# simple_sstc_halfbridge.net
KiCad netlist of a schematic drawn in EAGLE
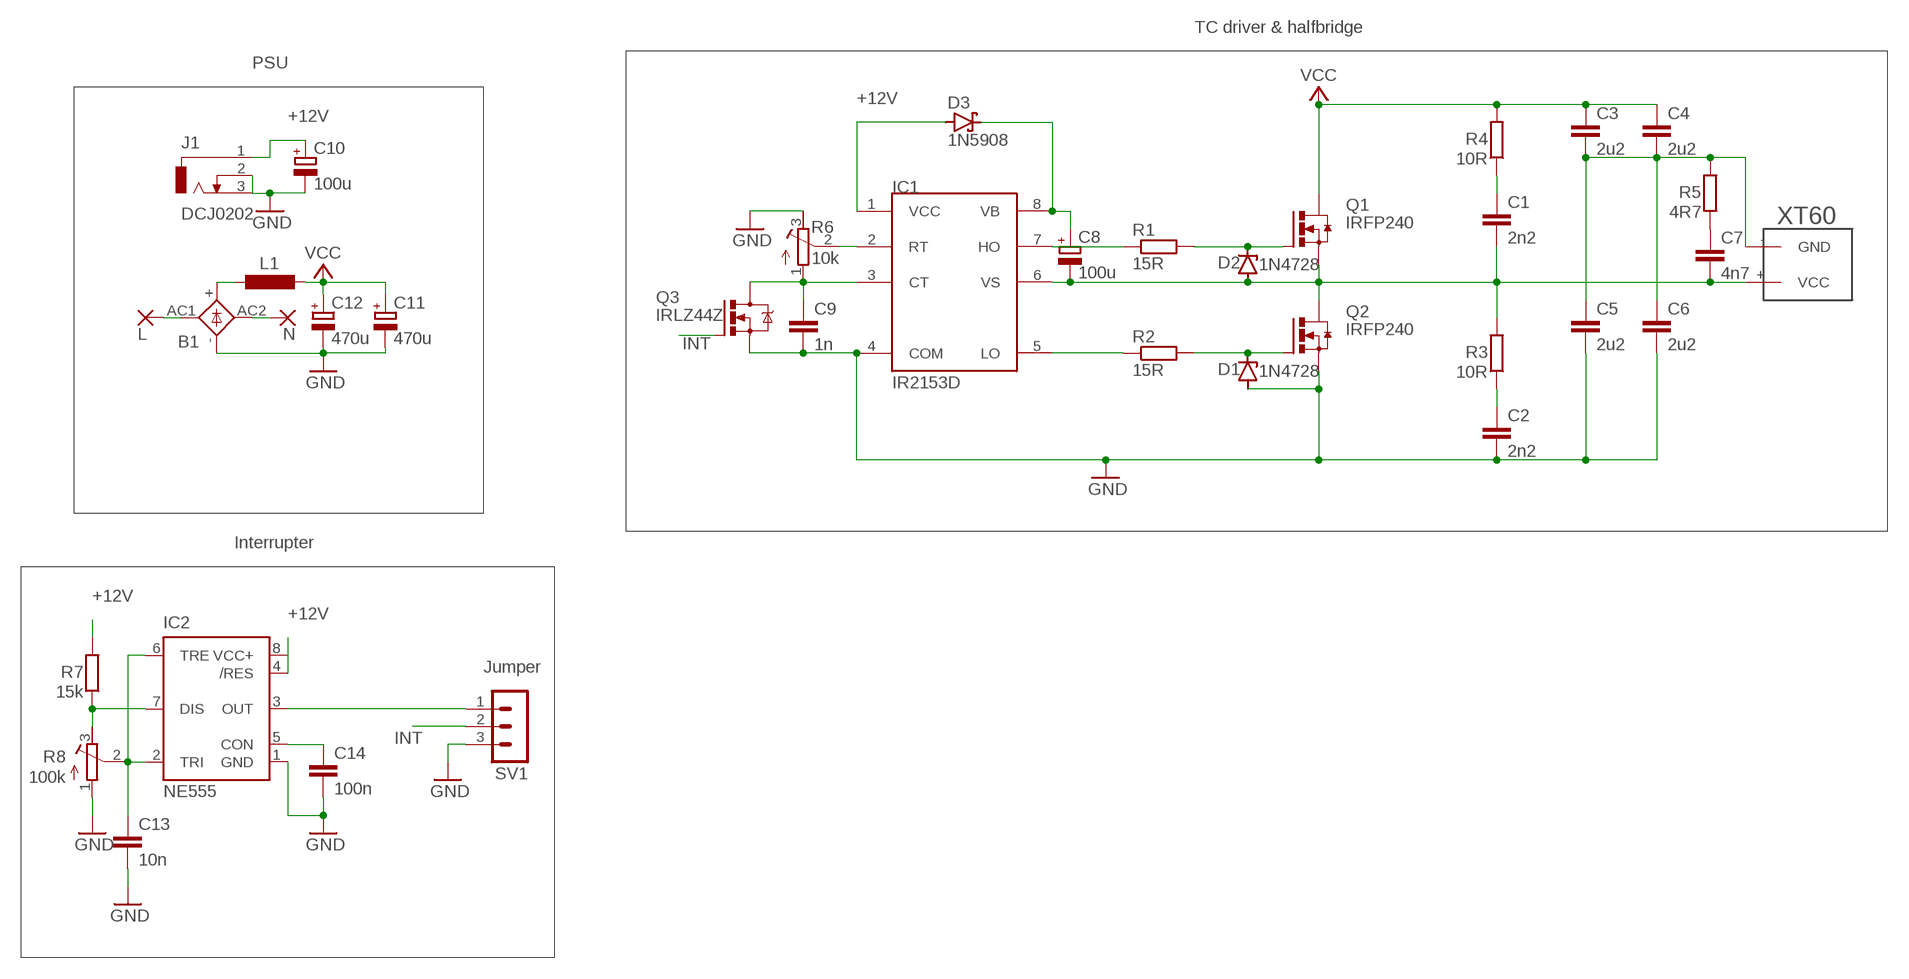
[diagram p0: schematic, sheet 1]

(export (version "E")
  (design (tool "Eeschema 10.0.6"))
  (components
    (comp (ref "B1")
      (value "2KBP")
      (footprint "eagle-import:2KBP")
      (libsource (lib "eagle-import") (part "2KBP"))
    )
    (comp (ref "C1")
      (value "2n2")
      (footprint "eagle-import:C7.5B3")
      (libsource (lib "eagle-import") (part "C7.5/3"))
    )
    (comp (ref "C2")
      (value "2n2")
      (footprint "eagle-import:C7.5B3")
      (libsource (lib "eagle-import") (part "C7.5/3"))
    )
    (comp (ref "C3")
      (value "2u2")
      (footprint "eagle-import:C22.5B6")
      (libsource (lib "eagle-import") (part "C22/6"))
    )
    (comp (ref "C4")
      (value "2u2")
      (footprint "eagle-import:C22.5B6")
      (libsource (lib "eagle-import") (part "C22/6"))
    )
    (comp (ref "C5")
      (value "2u2")
      (footprint "eagle-import:C22.5B6")
      (libsource (lib "eagle-import") (part "C22/6"))
    )
    (comp (ref "C6")
      (value "2u2")
      (footprint "eagle-import:C22.5B6")
      (libsource (lib "eagle-import") (part "C22/6"))
    )
    (comp (ref "C7")
      (value "4n7")
      (footprint "eagle-import:C7.5B3")
      (libsource (lib "eagle-import") (part "C7.5/3"))
    )
    (comp (ref "C8")
      (value "100u")
      (footprint "eagle-import:E2,5-7")
      (libsource (lib "eagle-import") (part "CPOL-EUE2.5-7"))
    )
    (comp (ref "C9")
      (value "1n")
      (footprint "eagle-import:C025-024X044")
      (libsource (lib "eagle-import") (part "C-EU025-024X044"))
    )
    (comp (ref "C10")
      (value "100u")
      (footprint "eagle-import:E2,5-7")
      (libsource (lib "eagle-import") (part "CPOL-EUE2.5-7"))
    )
    (comp (ref "C11")
      (value "470u")
      (footprint "eagle-import:EB35D")
      (libsource (lib "eagle-import") (part "CPOL-EUE10-35"))
    )
    (comp (ref "C12")
      (value "470u")
      (footprint "eagle-import:EB35D")
      (libsource (lib "eagle-import") (part "CPOL-EUE10-35"))
    )
    (comp (ref "C13")
      (value "10n")
      (footprint "eagle-import:C025-025X050")
      (libsource (lib "eagle-import") (part "C-EU025-025X050"))
    )
    (comp (ref "C14")
      (value "100n")
      (footprint "eagle-import:C025-025X050")
      (libsource (lib "eagle-import") (part "C-EU025-025X050"))
    )
    (comp (ref "D1")
      (value "1N4728")
      (footprint "eagle-import:DO41Z10")
      (libsource (lib "eagle-import") (part "1N4728"))
    )
    (comp (ref "D2")
      (value "1N4728")
      (footprint "eagle-import:DO41Z10")
      (libsource (lib "eagle-import") (part "1N4728"))
    )
    (comp (ref "D3")
      (value "1N5908")
      (footprint "eagle-import:C4111-15")
      (libsource (lib "eagle-import") (part "1N5908"))
    )
    (comp (ref "IC1")
      (value "IR2153D")
      (footprint "eagle-import:DIL08")
      (libsource (lib "eagle-import") (part "IR2153D"))
    )
    (comp (ref "IC2")
      (value "NE555")
      (footprint "eagle-import:DIL-08")
      (fields (field (name "MF") "Arrow Electronics") (field (name "MPN") "NE555N"))
      (libsource (lib "eagle-import") (part "NE555"))
    )
    (comp (ref "J1")
      (value "DCJ0202")
      (footprint "eagle-import:DCJ0202")
      (libsource (lib "eagle-import") (part "DCJ0202"))
    )
    (comp (ref "L")
      (value "3,81/1,4")
      (footprint "eagle-import:3,81_1,4")
      (libsource (lib "eagle-import") (part "3,81/1,4"))
    )
    (comp (ref "L1")
      (value "L-EUTJ4-U2")
      (footprint "eagle-import:TJ4-U2")
      (libsource (lib "eagle-import") (part "L-EUTJ4-U2"))
    )
    (comp (ref "N")
      (value "3,81/1,4")
      (footprint "eagle-import:3,81_1,4")
      (libsource (lib "eagle-import") (part "3,81/1,4"))
    )
    (comp (ref "Q1")
      (value "IRFP240")
      (footprint "eagle-import:TO247BV")
      (libsource (lib "eagle-import") (part "IRFP240"))
    )
    (comp (ref "Q2")
      (value "IRFP240")
      (footprint "eagle-import:TO247BV")
      (libsource (lib "eagle-import") (part "IRFP240"))
    )
    (comp (ref "Q3")
      (value "IRLZ44Z")
      (footprint "eagle-import:TO220BH")
      (libsource (lib "eagle-import") (part "IRLZ44Z"))
    )
    (comp (ref "R1")
      (value "15R")
      (footprint "eagle-import:VMTA55")
      (libsource (lib "eagle-import") (part "R-EU_VMTA55"))
    )
    (comp (ref "R2")
      (value "15R")
      (footprint "eagle-import:VMTA55")
      (libsource (lib "eagle-import") (part "R-EU_VMTA55"))
    )
    (comp (ref "R3")
      (value "10R")
      (footprint "eagle-import:V234_12")
      (libsource (lib "eagle-import") (part "R-EU_V234/12"))
    )
    (comp (ref "R4")
      (value "10R")
      (footprint "eagle-import:V234_12")
      (libsource (lib "eagle-import") (part "R-EU_V234/12"))
    )
    (comp (ref "R5")
      (value "4R7")
      (footprint "eagle-import:V234_12")
      (libsource (lib "eagle-import") (part "R-EU_V234/12"))
    )
    (comp (ref "R6")
      (value "10k")
      (footprint "eagle-import:RTRIM3339P")
      (libsource (lib "eagle-import") (part "R-TRIMM3339P"))
    )
    (comp (ref "R7")
      (value "15k")
      (footprint "eagle-import:VMTA55")
      (libsource (lib "eagle-import") (part "R-EU_VMTA55"))
    )
    (comp (ref "R8")
      (value "100k")
      (footprint "eagle-import:RTRIM3339P")
      (libsource (lib "eagle-import") (part "R-TRIMM3339P"))
    )
    (comp (ref "SV1")
      (value "MA03-1")
      (footprint "eagle-import:MA03-1")
      (libsource (lib "eagle-import") (part "MA03-1"))
    )
    (comp (ref "U$1")
      (value "XT60")
      (footprint "eagle-import:XT60")
      (libsource (lib "eagle-import") (part "XT60"))
    )
  )
  (nets
    (net (code "1") (name "/+12V") (class "Default")
      (node (ref "C10") (pin "+") (pinfunction "+_+") (pintype "passive"))
      (node (ref "D3") (pin "A") (pinfunction "A_A") (pintype "passive"))
      (node (ref "IC1") (pin "1") (pinfunction "VCC_1") (pintype "power_in"))
      (node (ref "IC2") (pin "4") (pinfunction "/RES_4") (pintype "input"))
      (node (ref "IC2") (pin "8") (pinfunction "VCC+_8") (pintype "power_in"))
      (node (ref "J1") (pin "1") (pinfunction "1_1") (pintype "passive"))
      (node (ref "R7") (pin "2") (pinfunction "2_2") (pintype "passive"))
    )
    (net (code "2") (name "/INT") (class "Default")
      (node (ref "Q3") (pin "G") (pinfunction "G_G") (pintype "passive"))
      (node (ref "SV1") (pin "2") (pinfunction "2_2") (pintype "passive"))
    )
    (net (code "3") (name "GND") (class "Default")
      (node (ref "B1") (pin "-") (pinfunction "-_-") (pintype "passive"))
      (node (ref "C10") (pin "-") (pinfunction "-_-") (pintype "passive"))
      (node (ref "C11") (pin "-") (pinfunction "-_-") (pintype "passive"))
      (node (ref "C12") (pin "-") (pinfunction "-_-") (pintype "passive"))
      (node (ref "C13") (pin "2") (pinfunction "2_2") (pintype "passive"))
      (node (ref "C14") (pin "2") (pinfunction "2_2") (pintype "passive"))
      (node (ref "C2") (pin "2") (pinfunction "2_2") (pintype "passive"))
      (node (ref "C5") (pin "2") (pinfunction "2_2") (pintype "passive"))
      (node (ref "C6") (pin "2") (pinfunction "2_2") (pintype "passive"))
      (node (ref "C9") (pin "2") (pinfunction "2_2") (pintype "passive"))
      (node (ref "D1") (pin "A") (pinfunction "A_A") (pintype "passive"))
      (node (ref "IC1") (pin "4") (pinfunction "COM_4") (pintype "power_in"))
      (node (ref "IC2") (pin "1") (pinfunction "GND_1") (pintype "power_in"))
      (node (ref "J1") (pin "2") (pinfunction "2_2") (pintype "passive"))
      (node (ref "J1") (pin "3") (pinfunction "3_3") (pintype "passive"))
      (node (ref "Q2") (pin "S") (pinfunction "S_S") (pintype "passive"))
      (node (ref "Q3") (pin "S") (pinfunction "S_S") (pintype "passive"))
      (node (ref "R6") (pin "3") (pinfunction "E_3") (pintype "passive"))
      (node (ref "R8") (pin "1") (pinfunction "A_1") (pintype "passive"))
      (node (ref "SV1") (pin "3") (pinfunction "3_3") (pintype "passive"))
    )
    (net (code "4") (name "Net-(B1-Pad+)") (class "Default")
      (node (ref "B1") (pin "+") (pinfunction "+_+") (pintype "passive"))
      (node (ref "L1") (pin "1") (pinfunction "1_1") (pintype "passive"))
    )
    (net (code "5") (name "Net-(C1-Pad1)") (class "Default")
      (node (ref "C1") (pin "1") (pinfunction "1_1") (pintype "passive"))
      (node (ref "R4") (pin "1") (pinfunction "1_1") (pintype "passive"))
    )
    (net (code "6") (name "Net-(C2-Pad1)") (class "Default")
      (node (ref "C2") (pin "1") (pinfunction "1_1") (pintype "passive"))
      (node (ref "R3") (pin "1") (pinfunction "1_1") (pintype "passive"))
    )
    (net (code "7") (name "Net-(C7-Pad1)") (class "Default")
      (node (ref "C7") (pin "1") (pinfunction "1_1") (pintype "passive"))
      (node (ref "R5") (pin "1") (pinfunction "1_1") (pintype "passive"))
    )
    (net (code "8") (name "Net-(D1-PadC)") (class "Default")
      (node (ref "D1") (pin "C") (pinfunction "C_C") (pintype "passive"))
      (node (ref "Q2") (pin "G") (pinfunction "G_G") (pintype "passive"))
      (node (ref "R2") (pin "2") (pinfunction "2_2") (pintype "passive"))
    )
    (net (code "9") (name "Net-(D2-PadC)") (class "Default")
      (node (ref "D2") (pin "C") (pinfunction "C_C") (pintype "passive"))
      (node (ref "Q1") (pin "G") (pinfunction "G_G") (pintype "passive"))
      (node (ref "R1") (pin "2") (pinfunction "2_2") (pintype "passive"))
    )
    (net (code "10") (name "Net-(IC1-CT)") (class "Default")
      (node (ref "C9") (pin "1") (pinfunction "1_1") (pintype "passive"))
      (node (ref "IC1") (pin "3") (pinfunction "CT_3") (pintype "input"))
      (node (ref "Q3") (pin "D") (pinfunction "D_D") (pintype "passive"))
      (node (ref "R6") (pin "1") (pinfunction "A_1") (pintype "passive"))
    )
    (net (code "11") (name "Net-(IC1-HO)") (class "Default")
      (node (ref "IC1") (pin "7") (pinfunction "HO_7") (pintype "output"))
      (node (ref "R1") (pin "1") (pinfunction "1_1") (pintype "passive"))
    )
    (net (code "12") (name "Net-(IC1-LO)") (class "Default")
      (node (ref "IC1") (pin "5") (pinfunction "LO_5") (pintype "output"))
      (node (ref "R2") (pin "1") (pinfunction "1_1") (pintype "passive"))
    )
    (net (code "13") (name "Net-(IC1-RT)") (class "Default")
      (node (ref "IC1") (pin "2") (pinfunction "RT_2") (pintype "output"))
      (node (ref "R6") (pin "2") (pinfunction "S_2") (pintype "passive"))
    )
    (net (code "14") (name "Net-(IC1-VB)") (class "Default")
      (node (ref "C8") (pin "+") (pinfunction "+_+") (pintype "passive"))
      (node (ref "D3") (pin "C") (pinfunction "C_C") (pintype "passive"))
      (node (ref "IC1") (pin "8") (pinfunction "VB_8") (pintype "power_in"))
    )
    (net (code "15") (name "Net-(IC1-VS)") (class "Default")
      (node (ref "C1") (pin "2") (pinfunction "2_2") (pintype "passive"))
      (node (ref "C7") (pin "2") (pinfunction "2_2") (pintype "passive"))
      (node (ref "C8") (pin "-") (pinfunction "-_-") (pintype "passive"))
      (node (ref "D2") (pin "A") (pinfunction "A_A") (pintype "passive"))
      (node (ref "IC1") (pin "6") (pinfunction "VS_6") (pintype "power_in"))
      (node (ref "Q1") (pin "S") (pinfunction "S_S") (pintype "passive"))
      (node (ref "Q2") (pin "D") (pinfunction "D_D") (pintype "passive"))
      (node (ref "R3") (pin "2") (pinfunction "2_2") (pintype "passive"))
      (node (ref "U$1") (pin "+") (pinfunction "VCC_+") (pintype "bidirectional"))
    )
    (net (code "16") (name "Net-(IC2-CON)") (class "Default")
      (node (ref "C14") (pin "1") (pinfunction "1_1") (pintype "passive"))
      (node (ref "IC2") (pin "5") (pinfunction "CON_5") (pintype "input"))
    )
    (net (code "17") (name "Net-(IC2-DIS)") (class "Default")
      (node (ref "IC2") (pin "7") (pinfunction "DIS_7") (pintype "input"))
      (node (ref "R7") (pin "1") (pinfunction "1_1") (pintype "passive"))
      (node (ref "R8") (pin "3") (pinfunction "E_3") (pintype "passive"))
    )
    (net (code "18") (name "Net-(IC2-OUT)") (class "Default")
      (node (ref "IC2") (pin "3") (pinfunction "OUT_3") (pintype "output"))
      (node (ref "SV1") (pin "1") (pinfunction "1_1") (pintype "passive"))
    )
    (net (code "19") (name "Net-(IC2-TRE)") (class "Default")
      (node (ref "C13") (pin "1") (pinfunction "1_1") (pintype "passive"))
      (node (ref "IC2") (pin "2") (pinfunction "TRI_2") (pintype "input"))
      (node (ref "IC2") (pin "6") (pinfunction "TRE_6") (pintype "input"))
      (node (ref "R8") (pin "2") (pinfunction "S_2") (pintype "passive"))
    )
    (net (code "20") (name "Net-(L-P)") (class "Default")
      (node (ref "B1") (pin "AC1") (pinfunction "AC1_AC1") (pintype "passive"))
      (node (ref "L") (pin "1") (pinfunction "P_1") (pintype "passive"))
    )
    (net (code "21") (name "Net-(N-P)") (class "Default")
      (node (ref "B1") (pin "AC2") (pinfunction "AC2_AC2") (pintype "passive"))
      (node (ref "N") (pin "1") (pinfunction "P_1") (pintype "passive"))
    )
    (net (code "22") (name "Net-(U$1-GND)") (class "Default")
      (node (ref "C3") (pin "2") (pinfunction "2_2") (pintype "passive"))
      (node (ref "C4") (pin "2") (pinfunction "2_2") (pintype "passive"))
      (node (ref "C5") (pin "1") (pinfunction "1_1") (pintype "passive"))
      (node (ref "C6") (pin "1") (pinfunction "1_1") (pintype "passive"))
      (node (ref "R5") (pin "2") (pinfunction "2_2") (pintype "passive"))
      (node (ref "U$1") (pin "-") (pinfunction "GND_-") (pintype "bidirectional"))
    )
    (net (code "23") (name "VCC") (class "Default")
      (node (ref "C11") (pin "+") (pinfunction "+_+") (pintype "passive"))
      (node (ref "C12") (pin "+") (pinfunction "+_+") (pintype "passive"))
      (node (ref "C3") (pin "1") (pinfunction "1_1") (pintype "passive"))
      (node (ref "C4") (pin "1") (pinfunction "1_1") (pintype "passive"))
      (node (ref "L1") (pin "2") (pinfunction "2_2") (pintype "passive"))
      (node (ref "Q1") (pin "D") (pinfunction "D_D") (pintype "passive"))
      (node (ref "R4") (pin "2") (pinfunction "2_2") (pintype "passive"))
    )
  )
)
